# sega.net
KiCad netlist of a schematic drawn in EAGLE
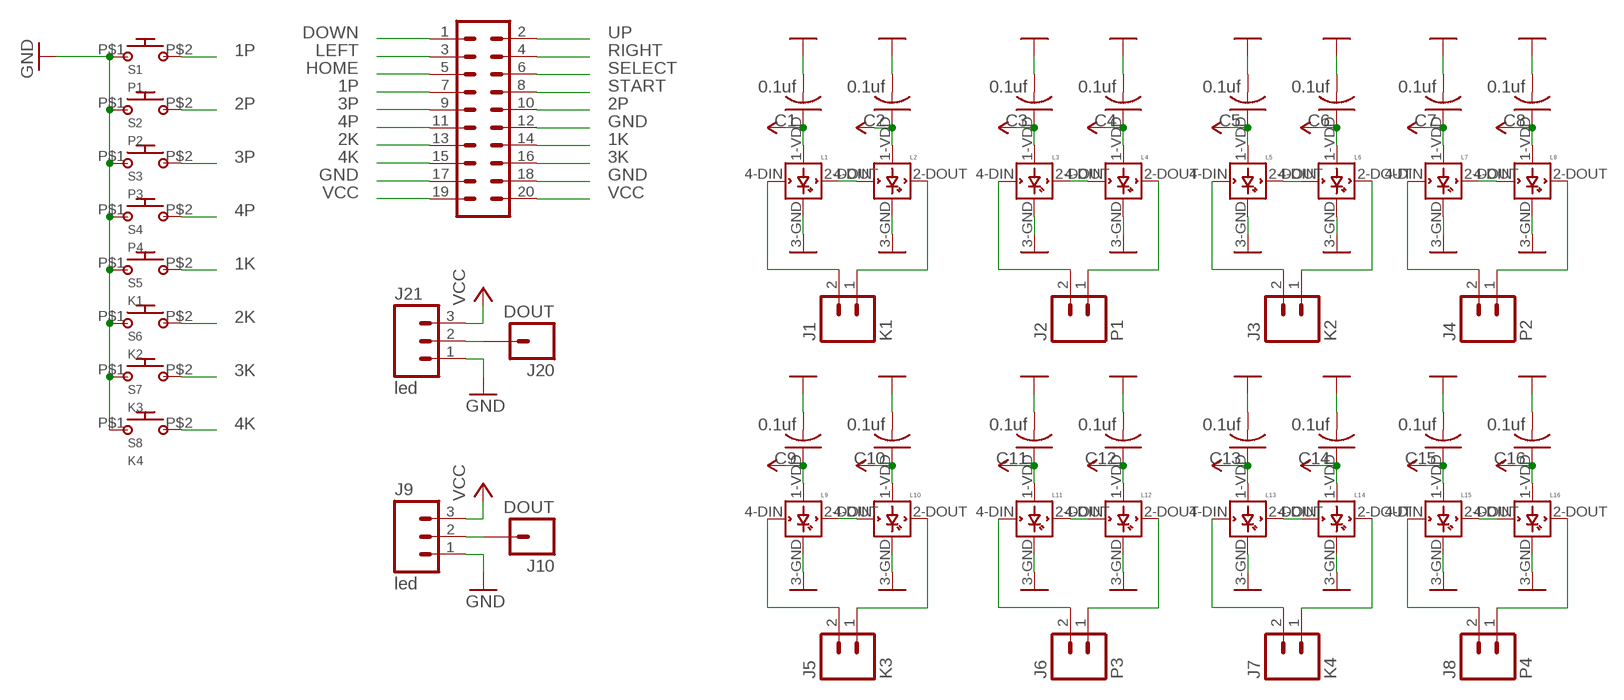
[diagram p0: schematic, sheet 1]

(export (version "E")
  (design (tool "Eeschema 10.0.6"))
  (components
    (comp (ref "C1")
      (value "0.1uf")
      (footprint "eagle-import:C0603K")
      (libsource (lib "eagle-import") (part "C-USC0603K"))
    )
    (comp (ref "C2")
      (value "0.1uf")
      (footprint "eagle-import:C0603K")
      (libsource (lib "eagle-import") (part "C-USC0603K"))
    )
    (comp (ref "C3")
      (value "0.1uf")
      (footprint "eagle-import:C0603K")
      (libsource (lib "eagle-import") (part "C-USC0603K"))
    )
    (comp (ref "C4")
      (value "0.1uf")
      (footprint "eagle-import:C0603K")
      (libsource (lib "eagle-import") (part "C-USC0603K"))
    )
    (comp (ref "C5")
      (value "0.1uf")
      (footprint "eagle-import:C0603K")
      (libsource (lib "eagle-import") (part "C-USC0603K"))
    )
    (comp (ref "C6")
      (value "0.1uf")
      (footprint "eagle-import:C0603K")
      (libsource (lib "eagle-import") (part "C-USC0603K"))
    )
    (comp (ref "C7")
      (value "0.1uf")
      (footprint "eagle-import:C0603K")
      (libsource (lib "eagle-import") (part "C-USC0603K"))
    )
    (comp (ref "C8")
      (value "0.1uf")
      (footprint "eagle-import:C0603K")
      (libsource (lib "eagle-import") (part "C-USC0603K"))
    )
    (comp (ref "C9")
      (value "0.1uf")
      (footprint "eagle-import:C0603K")
      (libsource (lib "eagle-import") (part "C-USC0603K"))
    )
    (comp (ref "C10")
      (value "0.1uf")
      (footprint "eagle-import:C0603K")
      (libsource (lib "eagle-import") (part "C-USC0603K"))
    )
    (comp (ref "C11")
      (value "0.1uf")
      (footprint "eagle-import:C0603K")
      (libsource (lib "eagle-import") (part "C-USC0603K"))
    )
    (comp (ref "C12")
      (value "0.1uf")
      (footprint "eagle-import:C0603K")
      (libsource (lib "eagle-import") (part "C-USC0603K"))
    )
    (comp (ref "C13")
      (value "0.1uf")
      (footprint "eagle-import:C0603K")
      (libsource (lib "eagle-import") (part "C-USC0603K"))
    )
    (comp (ref "C14")
      (value "0.1uf")
      (footprint "eagle-import:C0603K")
      (libsource (lib "eagle-import") (part "C-USC0603K"))
    )
    (comp (ref "C15")
      (value "0.1uf")
      (footprint "eagle-import:C0603K")
      (libsource (lib "eagle-import") (part "C-USC0603K"))
    )
    (comp (ref "C16")
      (value "0.1uf")
      (footprint "eagle-import:C0603K")
      (libsource (lib "eagle-import") (part "C-USC0603K"))
    )
    (comp (ref "J1")
      (value "K1")
      (footprint "eagle-import:1X02")
      (libsource (lib "eagle-import") (part "M02PTH"))
    )
    (comp (ref "J2")
      (value "P1")
      (footprint "eagle-import:1X02")
      (libsource (lib "eagle-import") (part "M02PTH"))
    )
    (comp (ref "J3")
      (value "K2")
      (footprint "eagle-import:1X02")
      (libsource (lib "eagle-import") (part "M02PTH"))
    )
    (comp (ref "J4")
      (value "P2")
      (footprint "eagle-import:1X02")
      (libsource (lib "eagle-import") (part "M02PTH"))
    )
    (comp (ref "J5")
      (value "K3")
      (footprint "eagle-import:1X02")
      (libsource (lib "eagle-import") (part "M02PTH"))
    )
    (comp (ref "J6")
      (value "P3")
      (footprint "eagle-import:1X02")
      (libsource (lib "eagle-import") (part "M02PTH"))
    )
    (comp (ref "J7")
      (value "K4")
      (footprint "eagle-import:1X02")
      (libsource (lib "eagle-import") (part "M02PTH"))
    )
    (comp (ref "J8")
      (value "P4")
      (footprint "eagle-import:1X02")
      (libsource (lib "eagle-import") (part "M02PTH"))
    )
    (comp (ref "J9")
      (value "led")
      (footprint "eagle-import:JST-3-PTH-VERT")
      (libsource (lib "eagle-import") (part "M03JST-PTH-VERT"))
    )
    (comp (ref "J10")
      (value "DOUT")
      (footprint "eagle-import:1X01")
      (libsource (lib "eagle-import") (part "M01PTH"))
    )
    (comp (ref "J20")
      (value "DOUT")
      (footprint "eagle-import:1X01")
      (libsource (lib "eagle-import") (part "M01PTH"))
    )
    (comp (ref "J21")
      (value "led")
      (footprint "eagle-import:JST-3-PTH-VERT")
      (libsource (lib "eagle-import") (part "M03JST-PTH-VERT"))
    )
    (comp (ref "L1")
      (value "WS2812B")
      (footprint "eagle-import:WS2812B")
      (libsource (lib "eagle-import") (part "WS2812B"))
    )
    (comp (ref "L2")
      (value "WS2812B")
      (footprint "eagle-import:WS2812B")
      (libsource (lib "eagle-import") (part "WS2812B"))
    )
    (comp (ref "L3")
      (value "WS2812B")
      (footprint "eagle-import:WS2812B")
      (libsource (lib "eagle-import") (part "WS2812B"))
    )
    (comp (ref "L4")
      (value "WS2812B")
      (footprint "eagle-import:WS2812B")
      (libsource (lib "eagle-import") (part "WS2812B"))
    )
    (comp (ref "L5")
      (value "WS2812B")
      (footprint "eagle-import:WS2812B")
      (libsource (lib "eagle-import") (part "WS2812B"))
    )
    (comp (ref "L6")
      (value "WS2812B")
      (footprint "eagle-import:WS2812B")
      (libsource (lib "eagle-import") (part "WS2812B"))
    )
    (comp (ref "L7")
      (value "WS2812B")
      (footprint "eagle-import:WS2812B")
      (libsource (lib "eagle-import") (part "WS2812B"))
    )
    (comp (ref "L8")
      (value "WS2812B")
      (footprint "eagle-import:WS2812B")
      (libsource (lib "eagle-import") (part "WS2812B"))
    )
    (comp (ref "L9")
      (value "WS2812B")
      (footprint "eagle-import:WS2812B")
      (libsource (lib "eagle-import") (part "WS2812B"))
    )
    (comp (ref "L10")
      (value "WS2812B")
      (footprint "eagle-import:WS2812B")
      (libsource (lib "eagle-import") (part "WS2812B"))
    )
    (comp (ref "L11")
      (value "WS2812B")
      (footprint "eagle-import:WS2812B")
      (libsource (lib "eagle-import") (part "WS2812B"))
    )
    (comp (ref "L12")
      (value "WS2812B")
      (footprint "eagle-import:WS2812B")
      (libsource (lib "eagle-import") (part "WS2812B"))
    )
    (comp (ref "L13")
      (value "WS2812B")
      (footprint "eagle-import:WS2812B")
      (libsource (lib "eagle-import") (part "WS2812B"))
    )
    (comp (ref "L14")
      (value "WS2812B")
      (footprint "eagle-import:WS2812B")
      (libsource (lib "eagle-import") (part "WS2812B"))
    )
    (comp (ref "L15")
      (value "WS2812B")
      (footprint "eagle-import:WS2812B")
      (libsource (lib "eagle-import") (part "WS2812B"))
    )
    (comp (ref "L16")
      (value "WS2812B")
      (footprint "eagle-import:WS2812B")
      (libsource (lib "eagle-import") (part "WS2812B"))
    )
    (comp (ref "S1")
      (value "P1")
      (footprint "eagle-import:SANWA_24MM")
      (libsource (lib "eagle-import") (part "SANWA_OBSC_24_CW"))
    )
    (comp (ref "S2")
      (value "P2")
      (footprint "eagle-import:SANWA_24MM")
      (libsource (lib "eagle-import") (part "SANWA_OBSC_24_CW"))
    )
    (comp (ref "S3")
      (value "P3")
      (footprint "eagle-import:SANWA_24MM")
      (libsource (lib "eagle-import") (part "SANWA_OBSC_24_CW"))
    )
    (comp (ref "S4")
      (value "P4")
      (footprint "eagle-import:SANWA_24MM")
      (libsource (lib "eagle-import") (part "SANWA_OBSC_24_CW"))
    )
    (comp (ref "S5")
      (value "K1")
      (footprint "eagle-import:SANWA_24MM")
      (libsource (lib "eagle-import") (part "SANWA_OBSC_24_CW"))
    )
    (comp (ref "S6")
      (value "K2")
      (footprint "eagle-import:SANWA_24MM")
      (libsource (lib "eagle-import") (part "SANWA_OBSC_24_CW"))
    )
    (comp (ref "S7")
      (value "K3")
      (footprint "eagle-import:SANWA_24MM")
      (libsource (lib "eagle-import") (part "SANWA_OBSC_24_CW"))
    )
    (comp (ref "S8")
      (value "K4")
      (footprint "eagle-import:SANWA_24MM")
      (libsource (lib "eagle-import") (part "SANWA_OBSC_24_CW"))
    )
    (comp (ref "U$1")
      (value "M10X2ROUND_NOSILK")
      (footprint "eagle-import:2X10_ROUND_NOSILK")
      (libsource (lib "eagle-import") (part "M10X2ROUND_NOSILK"))
    )
  )
  (nets
    (net (code "1") (name "/1K") (class "Default")
      (node (ref "S5") (pin "P$2") (pinfunction "P$2_P$2") (pintype "passive"))
      (node (ref "U$1") (pin "14") (pinfunction "14_14") (pintype "passive"))
    )
    (net (code "2") (name "/1P") (class "Default")
      (node (ref "S1") (pin "P$2") (pinfunction "P$2_P$2") (pintype "passive"))
      (node (ref "U$1") (pin "7") (pinfunction "7_7") (pintype "passive"))
    )
    (net (code "3") (name "/2K") (class "Default")
      (node (ref "S6") (pin "P$2") (pinfunction "P$2_P$2") (pintype "passive"))
      (node (ref "U$1") (pin "13") (pinfunction "13_13") (pintype "passive"))
    )
    (net (code "4") (name "/2P") (class "Default")
      (node (ref "S2") (pin "P$2") (pinfunction "P$2_P$2") (pintype "passive"))
      (node (ref "U$1") (pin "10") (pinfunction "10_10") (pintype "passive"))
    )
    (net (code "5") (name "/3K") (class "Default")
      (node (ref "S7") (pin "P$2") (pinfunction "P$2_P$2") (pintype "passive"))
      (node (ref "U$1") (pin "16") (pinfunction "16_16") (pintype "passive"))
    )
    (net (code "6") (name "/3P") (class "Default")
      (node (ref "S3") (pin "P$2") (pinfunction "P$2_P$2") (pintype "passive"))
      (node (ref "U$1") (pin "9") (pinfunction "9_9") (pintype "passive"))
    )
    (net (code "7") (name "/4K") (class "Default")
      (node (ref "S8") (pin "P$2") (pinfunction "P$2_P$2") (pintype "passive"))
      (node (ref "U$1") (pin "15") (pinfunction "15_15") (pintype "passive"))
    )
    (net (code "8") (name "/4P") (class "Default")
      (node (ref "S4") (pin "P$2") (pinfunction "P$2_P$2") (pintype "passive"))
      (node (ref "U$1") (pin "11") (pinfunction "11_11") (pintype "passive"))
    )
    (net (code "9") (name "/DOWN") (class "Default")
      (node (ref "U$1") (pin "1") (pinfunction "1_1") (pintype "passive"))
    )
    (net (code "10") (name "/HOME") (class "Default")
      (node (ref "U$1") (pin "5") (pinfunction "5_5") (pintype "passive"))
    )
    (net (code "11") (name "/LEFT") (class "Default")
      (node (ref "U$1") (pin "3") (pinfunction "3_3") (pintype "passive"))
    )
    (net (code "12") (name "/RIGHT") (class "Default")
      (node (ref "U$1") (pin "4") (pinfunction "4_4") (pintype "passive"))
    )
    (net (code "13") (name "/SELECT") (class "Default")
      (node (ref "U$1") (pin "6") (pinfunction "6_6") (pintype "passive"))
    )
    (net (code "14") (name "/START") (class "Default")
      (node (ref "U$1") (pin "8") (pinfunction "8_8") (pintype "passive"))
    )
    (net (code "15") (name "/UP") (class "Default")
      (node (ref "U$1") (pin "2") (pinfunction "2_2") (pintype "passive"))
    )
    (net (code "16") (name "GND") (class "Default")
      (node (ref "C1") (pin "2") (pinfunction "2_2") (pintype "passive"))
      (node (ref "C10") (pin "2") (pinfunction "2_2") (pintype "passive"))
      (node (ref "C11") (pin "2") (pinfunction "2_2") (pintype "passive"))
      (node (ref "C12") (pin "2") (pinfunction "2_2") (pintype "passive"))
      (node (ref "C13") (pin "2") (pinfunction "2_2") (pintype "passive"))
      (node (ref "C14") (pin "2") (pinfunction "2_2") (pintype "passive"))
      (node (ref "C15") (pin "2") (pinfunction "2_2") (pintype "passive"))
      (node (ref "C16") (pin "2") (pinfunction "2_2") (pintype "passive"))
      (node (ref "C2") (pin "2") (pinfunction "2_2") (pintype "passive"))
      (node (ref "C3") (pin "2") (pinfunction "2_2") (pintype "passive"))
      (node (ref "C4") (pin "2") (pinfunction "2_2") (pintype "passive"))
      (node (ref "C5") (pin "2") (pinfunction "2_2") (pintype "passive"))
      (node (ref "C6") (pin "2") (pinfunction "2_2") (pintype "passive"))
      (node (ref "C7") (pin "2") (pinfunction "2_2") (pintype "passive"))
      (node (ref "C8") (pin "2") (pinfunction "2_2") (pintype "passive"))
      (node (ref "C9") (pin "2") (pinfunction "2_2") (pintype "passive"))
      (node (ref "J21") (pin "1") (pinfunction "1_1") (pintype "passive"))
      (node (ref "J9") (pin "1") (pinfunction "1_1") (pintype "passive"))
      (node (ref "L1") (pin "3-GND") (pinfunction "GND_3-GND") (pintype "bidirectional"))
      (node (ref "L10") (pin "3-GND") (pinfunction "GND_3-GND") (pintype "bidirectional"))
      (node (ref "L11") (pin "3-GND") (pinfunction "GND_3-GND") (pintype "bidirectional"))
      (node (ref "L12") (pin "3-GND") (pinfunction "GND_3-GND") (pintype "bidirectional"))
      (node (ref "L13") (pin "3-GND") (pinfunction "GND_3-GND") (pintype "bidirectional"))
      (node (ref "L14") (pin "3-GND") (pinfunction "GND_3-GND") (pintype "bidirectional"))
      (node (ref "L15") (pin "3-GND") (pinfunction "GND_3-GND") (pintype "bidirectional"))
      (node (ref "L16") (pin "3-GND") (pinfunction "GND_3-GND") (pintype "bidirectional"))
      (node (ref "L2") (pin "3-GND") (pinfunction "GND_3-GND") (pintype "bidirectional"))
      (node (ref "L3") (pin "3-GND") (pinfunction "GND_3-GND") (pintype "bidirectional"))
      (node (ref "L4") (pin "3-GND") (pinfunction "GND_3-GND") (pintype "bidirectional"))
      (node (ref "L5") (pin "3-GND") (pinfunction "GND_3-GND") (pintype "bidirectional"))
      (node (ref "L6") (pin "3-GND") (pinfunction "GND_3-GND") (pintype "bidirectional"))
      (node (ref "L7") (pin "3-GND") (pinfunction "GND_3-GND") (pintype "bidirectional"))
      (node (ref "L8") (pin "3-GND") (pinfunction "GND_3-GND") (pintype "bidirectional"))
      (node (ref "L9") (pin "3-GND") (pinfunction "GND_3-GND") (pintype "bidirectional"))
      (node (ref "S1") (pin "P$1") (pinfunction "P$1_P$1") (pintype "passive"))
      (node (ref "S2") (pin "P$1") (pinfunction "P$1_P$1") (pintype "passive"))
      (node (ref "S3") (pin "P$1") (pinfunction "P$1_P$1") (pintype "passive"))
      (node (ref "S4") (pin "P$1") (pinfunction "P$1_P$1") (pintype "passive"))
      (node (ref "S5") (pin "P$1") (pinfunction "P$1_P$1") (pintype "passive"))
      (node (ref "S6") (pin "P$1") (pinfunction "P$1_P$1") (pintype "passive"))
      (node (ref "S7") (pin "P$1") (pinfunction "P$1_P$1") (pintype "passive"))
      (node (ref "S8") (pin "P$1") (pinfunction "P$1_P$1") (pintype "passive"))
      (node (ref "U$1") (pin "12") (pinfunction "12_12") (pintype "passive"))
      (node (ref "U$1") (pin "17") (pinfunction "17_17") (pintype "passive"))
      (node (ref "U$1") (pin "18") (pinfunction "18_18") (pintype "passive"))
    )
    (net (code "17") (name "Net-(J10-Pad1)") (class "Default")
      (node (ref "J10") (pin "1") (pinfunction "1_1") (pintype "passive"))
      (node (ref "J9") (pin "2") (pinfunction "2_2") (pintype "passive"))
    )
    (net (code "18") (name "Net-(J20-Pad1)") (class "Default")
      (node (ref "J20") (pin "1") (pinfunction "1_1") (pintype "passive"))
      (node (ref "J21") (pin "2") (pinfunction "2_2") (pintype "passive"))
    )
    (net (code "19") (name "Net-(L1-DIN)") (class "Default")
      (node (ref "J1") (pin "2") (pinfunction "2_2") (pintype "passive"))
      (node (ref "L1") (pin "4-DIN") (pinfunction "DIN_4-DIN") (pintype "input"))
    )
    (net (code "20") (name "Net-(L1-DOUT)") (class "Default")
      (node (ref "L1") (pin "2-DOUT") (pinfunction "DOUT_2-DOUT") (pintype "output"))
      (node (ref "L2") (pin "4-DIN") (pinfunction "DIN_4-DIN") (pintype "input"))
    )
    (net (code "21") (name "Net-(L2-DOUT)") (class "Default")
      (node (ref "J1") (pin "1") (pinfunction "1_1") (pintype "passive"))
      (node (ref "L2") (pin "2-DOUT") (pinfunction "DOUT_2-DOUT") (pintype "output"))
    )
    (net (code "22") (name "Net-(L3-DIN)") (class "Default")
      (node (ref "J2") (pin "2") (pinfunction "2_2") (pintype "passive"))
      (node (ref "L3") (pin "4-DIN") (pinfunction "DIN_4-DIN") (pintype "input"))
    )
    (net (code "23") (name "Net-(L3-DOUT)") (class "Default")
      (node (ref "L3") (pin "2-DOUT") (pinfunction "DOUT_2-DOUT") (pintype "output"))
      (node (ref "L4") (pin "4-DIN") (pinfunction "DIN_4-DIN") (pintype "input"))
    )
    (net (code "24") (name "Net-(L4-DOUT)") (class "Default")
      (node (ref "J2") (pin "1") (pinfunction "1_1") (pintype "passive"))
      (node (ref "L4") (pin "2-DOUT") (pinfunction "DOUT_2-DOUT") (pintype "output"))
    )
    (net (code "25") (name "Net-(L5-DIN)") (class "Default")
      (node (ref "J3") (pin "2") (pinfunction "2_2") (pintype "passive"))
      (node (ref "L5") (pin "4-DIN") (pinfunction "DIN_4-DIN") (pintype "input"))
    )
    (net (code "26") (name "Net-(L5-DOUT)") (class "Default")
      (node (ref "L5") (pin "2-DOUT") (pinfunction "DOUT_2-DOUT") (pintype "output"))
      (node (ref "L6") (pin "4-DIN") (pinfunction "DIN_4-DIN") (pintype "input"))
    )
    (net (code "27") (name "Net-(L6-DOUT)") (class "Default")
      (node (ref "J3") (pin "1") (pinfunction "1_1") (pintype "passive"))
      (node (ref "L6") (pin "2-DOUT") (pinfunction "DOUT_2-DOUT") (pintype "output"))
    )
    (net (code "28") (name "Net-(L7-DIN)") (class "Default")
      (node (ref "J4") (pin "2") (pinfunction "2_2") (pintype "passive"))
      (node (ref "L7") (pin "4-DIN") (pinfunction "DIN_4-DIN") (pintype "input"))
    )
    (net (code "29") (name "Net-(L7-DOUT)") (class "Default")
      (node (ref "L7") (pin "2-DOUT") (pinfunction "DOUT_2-DOUT") (pintype "output"))
      (node (ref "L8") (pin "4-DIN") (pinfunction "DIN_4-DIN") (pintype "input"))
    )
    (net (code "30") (name "Net-(L8-DOUT)") (class "Default")
      (node (ref "J4") (pin "1") (pinfunction "1_1") (pintype "passive"))
      (node (ref "L8") (pin "2-DOUT") (pinfunction "DOUT_2-DOUT") (pintype "output"))
    )
    (net (code "31") (name "Net-(L9-DIN)") (class "Default")
      (node (ref "J5") (pin "2") (pinfunction "2_2") (pintype "passive"))
      (node (ref "L9") (pin "4-DIN") (pinfunction "DIN_4-DIN") (pintype "input"))
    )
    (net (code "32") (name "Net-(L10-DIN)") (class "Default")
      (node (ref "L10") (pin "4-DIN") (pinfunction "DIN_4-DIN") (pintype "input"))
      (node (ref "L9") (pin "2-DOUT") (pinfunction "DOUT_2-DOUT") (pintype "output"))
    )
    (net (code "33") (name "Net-(L10-DOUT)") (class "Default")
      (node (ref "J5") (pin "1") (pinfunction "1_1") (pintype "passive"))
      (node (ref "L10") (pin "2-DOUT") (pinfunction "DOUT_2-DOUT") (pintype "output"))
    )
    (net (code "34") (name "Net-(L11-DIN)") (class "Default")
      (node (ref "J6") (pin "2") (pinfunction "2_2") (pintype "passive"))
      (node (ref "L11") (pin "4-DIN") (pinfunction "DIN_4-DIN") (pintype "input"))
    )
    (net (code "35") (name "Net-(L11-DOUT)") (class "Default")
      (node (ref "L11") (pin "2-DOUT") (pinfunction "DOUT_2-DOUT") (pintype "output"))
      (node (ref "L12") (pin "4-DIN") (pinfunction "DIN_4-DIN") (pintype "input"))
    )
    (net (code "36") (name "Net-(L12-DOUT)") (class "Default")
      (node (ref "J6") (pin "1") (pinfunction "1_1") (pintype "passive"))
      (node (ref "L12") (pin "2-DOUT") (pinfunction "DOUT_2-DOUT") (pintype "output"))
    )
    (net (code "37") (name "Net-(L13-DIN)") (class "Default")
      (node (ref "J7") (pin "2") (pinfunction "2_2") (pintype "passive"))
      (node (ref "L13") (pin "4-DIN") (pinfunction "DIN_4-DIN") (pintype "input"))
    )
    (net (code "38") (name "Net-(L13-DOUT)") (class "Default")
      (node (ref "L13") (pin "2-DOUT") (pinfunction "DOUT_2-DOUT") (pintype "output"))
      (node (ref "L14") (pin "4-DIN") (pinfunction "DIN_4-DIN") (pintype "input"))
    )
    (net (code "39") (name "Net-(L14-DOUT)") (class "Default")
      (node (ref "J7") (pin "1") (pinfunction "1_1") (pintype "passive"))
      (node (ref "L14") (pin "2-DOUT") (pinfunction "DOUT_2-DOUT") (pintype "output"))
    )
    (net (code "40") (name "Net-(L15-DIN)") (class "Default")
      (node (ref "J8") (pin "2") (pinfunction "2_2") (pintype "passive"))
      (node (ref "L15") (pin "4-DIN") (pinfunction "DIN_4-DIN") (pintype "input"))
    )
    (net (code "41") (name "Net-(L15-DOUT)") (class "Default")
      (node (ref "L15") (pin "2-DOUT") (pinfunction "DOUT_2-DOUT") (pintype "output"))
      (node (ref "L16") (pin "4-DIN") (pinfunction "DIN_4-DIN") (pintype "input"))
    )
    (net (code "42") (name "Net-(L16-DOUT)") (class "Default")
      (node (ref "J8") (pin "1") (pinfunction "1_1") (pintype "passive"))
      (node (ref "L16") (pin "2-DOUT") (pinfunction "DOUT_2-DOUT") (pintype "output"))
    )
    (net (code "43") (name "VCC") (class "Default")
      (node (ref "C1") (pin "1") (pinfunction "1_1") (pintype "passive"))
      (node (ref "C10") (pin "1") (pinfunction "1_1") (pintype "passive"))
      (node (ref "C11") (pin "1") (pinfunction "1_1") (pintype "passive"))
      (node (ref "C12") (pin "1") (pinfunction "1_1") (pintype "passive"))
      (node (ref "C13") (pin "1") (pinfunction "1_1") (pintype "passive"))
      (node (ref "C14") (pin "1") (pinfunction "1_1") (pintype "passive"))
      (node (ref "C15") (pin "1") (pinfunction "1_1") (pintype "passive"))
      (node (ref "C16") (pin "1") (pinfunction "1_1") (pintype "passive"))
      (node (ref "C2") (pin "1") (pinfunction "1_1") (pintype "passive"))
      (node (ref "C3") (pin "1") (pinfunction "1_1") (pintype "passive"))
      (node (ref "C4") (pin "1") (pinfunction "1_1") (pintype "passive"))
      (node (ref "C5") (pin "1") (pinfunction "1_1") (pintype "passive"))
      (node (ref "C6") (pin "1") (pinfunction "1_1") (pintype "passive"))
      (node (ref "C7") (pin "1") (pinfunction "1_1") (pintype "passive"))
      (node (ref "C8") (pin "1") (pinfunction "1_1") (pintype "passive"))
      (node (ref "C9") (pin "1") (pinfunction "1_1") (pintype "passive"))
      (node (ref "J21") (pin "3") (pinfunction "3_3") (pintype "passive"))
      (node (ref "J9") (pin "3") (pinfunction "3_3") (pintype "passive"))
      (node (ref "L1") (pin "1-VDD") (pinfunction "VDD_1-VDD") (pintype "bidirectional"))
      (node (ref "L10") (pin "1-VDD") (pinfunction "VDD_1-VDD") (pintype "bidirectional"))
      (node (ref "L11") (pin "1-VDD") (pinfunction "VDD_1-VDD") (pintype "bidirectional"))
      (node (ref "L12") (pin "1-VDD") (pinfunction "VDD_1-VDD") (pintype "bidirectional"))
      (node (ref "L13") (pin "1-VDD") (pinfunction "VDD_1-VDD") (pintype "bidirectional"))
      (node (ref "L14") (pin "1-VDD") (pinfunction "VDD_1-VDD") (pintype "bidirectional"))
      (node (ref "L15") (pin "1-VDD") (pinfunction "VDD_1-VDD") (pintype "bidirectional"))
      (node (ref "L16") (pin "1-VDD") (pinfunction "VDD_1-VDD") (pintype "bidirectional"))
      (node (ref "L2") (pin "1-VDD") (pinfunction "VDD_1-VDD") (pintype "bidirectional"))
      (node (ref "L3") (pin "1-VDD") (pinfunction "VDD_1-VDD") (pintype "bidirectional"))
      (node (ref "L4") (pin "1-VDD") (pinfunction "VDD_1-VDD") (pintype "bidirectional"))
      (node (ref "L5") (pin "1-VDD") (pinfunction "VDD_1-VDD") (pintype "bidirectional"))
      (node (ref "L6") (pin "1-VDD") (pinfunction "VDD_1-VDD") (pintype "bidirectional"))
      (node (ref "L7") (pin "1-VDD") (pinfunction "VDD_1-VDD") (pintype "bidirectional"))
      (node (ref "L8") (pin "1-VDD") (pinfunction "VDD_1-VDD") (pintype "bidirectional"))
      (node (ref "L9") (pin "1-VDD") (pinfunction "VDD_1-VDD") (pintype "bidirectional"))
      (node (ref "U$1") (pin "19") (pinfunction "19_19") (pintype "passive"))
      (node (ref "U$1") (pin "20") (pinfunction "20_20") (pintype "passive"))
    )
  )
)
